# SCH_WINGLET_DISP.net
KiCad netlist of a schematic drawn in Altium Designer
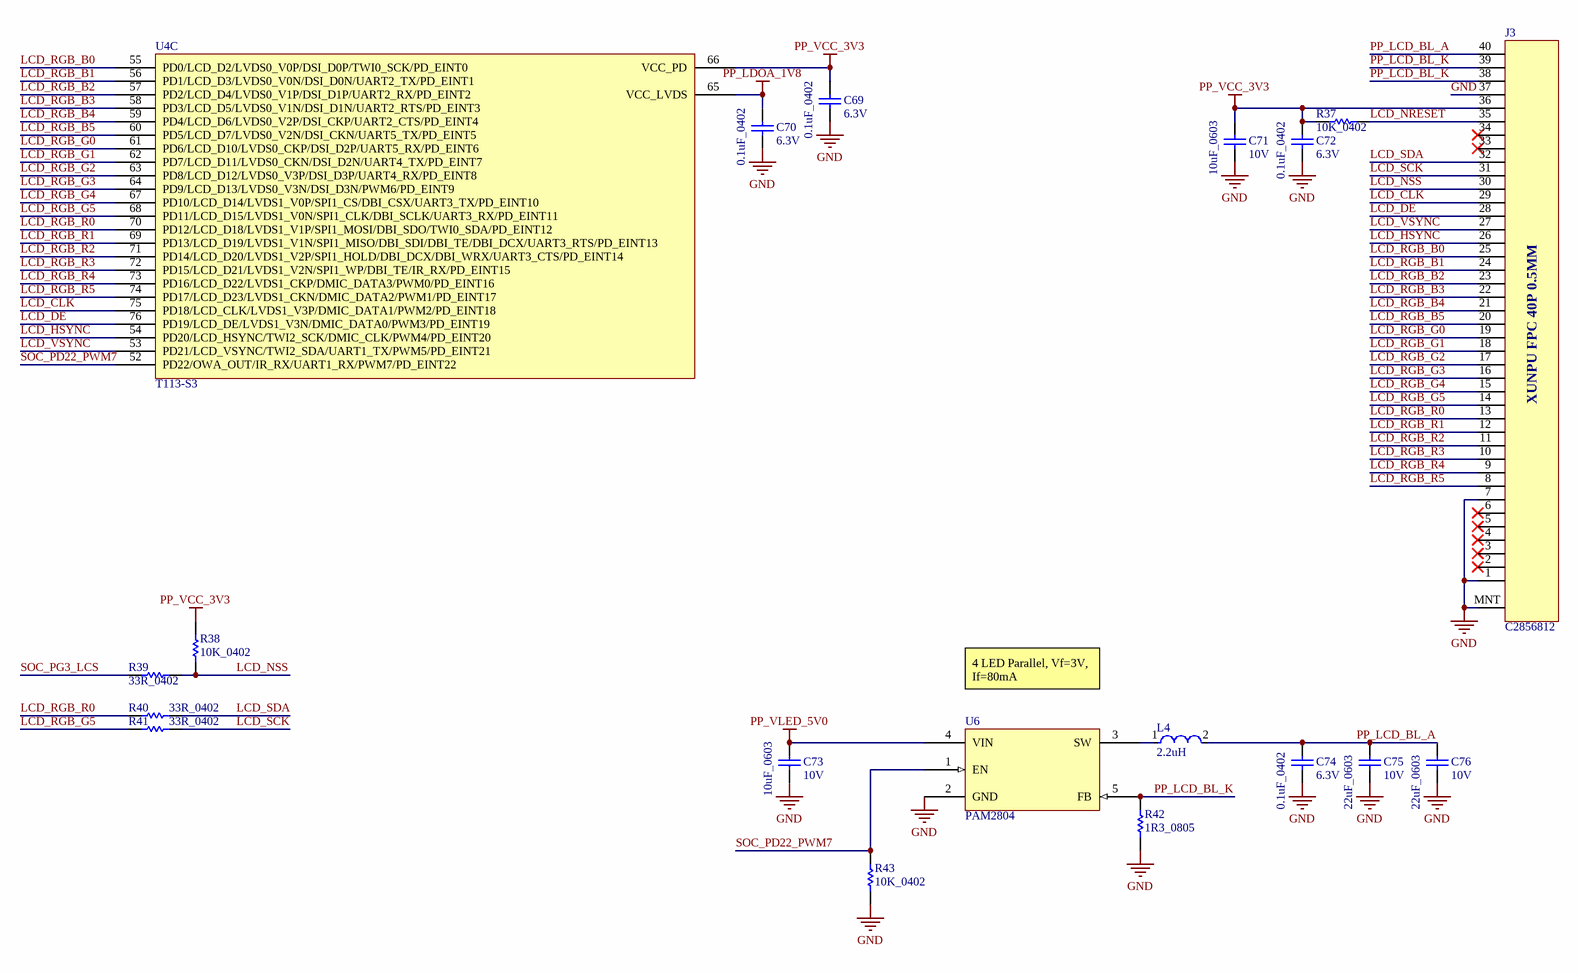
[diagram p0: SCH_WINGLET_DISP.SchDoc]

(export (version "E")
  (design (tool "Eeschema 10.0.6"))
  (components
    (comp (ref "C69")
      (value "0.1uF_0402")
      (footprint "CAPC1005X56X25NL10T15")
      (description "04026D104KAT2A")
      (fields (field (name "MANUFACTURER") "AVX Interconnect / Elco") (field (name "VOLTAGE RATING") "6.3V"))
      (libsource (lib "Altium Content Vault") (part "CAP"))
    )
    (comp (ref "C70")
      (value "0.1uF_0402")
      (footprint "CAPC1005X56X25NL10T15")
      (description "04026D104KAT2A")
      (fields (field (name "MANUFACTURER") "AVX Interconnect / Elco") (field (name "VOLTAGE RATING") "6.3V"))
      (libsource (lib "Altium Content Vault") (part "CAP"))
    )
    (comp (ref "C71")
      (value "10uF_0603")
      (footprint "CAPC1609X100X15NL20")
      (fields
        (field (name "PART NUMBER") "TACL106M006XTA")
        (field (name "MANUFACTURER") "AVX Interconnect / Elco")
        (field (name "VOLTAGE RATING") "10V")
      )
      (libsource (lib "Altium Content Vault") (part "CAP"))
    )
    (comp (ref "C72")
      (value "0.1uF_0402")
      (footprint "CAPC1005X56X25NL10T15")
      (description "04026D104KAT2A")
      (fields (field (name "MANUFACTURER") "AVX Interconnect / Elco") (field (name "VOLTAGE RATING") "6.3V"))
      (libsource (lib "Altium Content Vault") (part "CAP"))
    )
    (comp (ref "C73")
      (value "10uF_0603")
      (footprint "CAPC1609X100X15NL20")
      (fields
        (field (name "PART NUMBER") "TACL106M006XTA")
        (field (name "MANUFACTURER") "AVX Interconnect / Elco")
        (field (name "VOLTAGE RATING") "10V")
      )
      (libsource (lib "Altium Content Vault") (part "CAP"))
    )
    (comp (ref "C74")
      (value "0.1uF_0402")
      (footprint "CAPC1005X56X25NL10T15")
      (description "04026D104KAT2A")
      (fields (field (name "MANUFACTURER") "AVX Interconnect / Elco") (field (name "VOLTAGE RATING") "6.3V"))
      (libsource (lib "Altium Content Vault") (part "CAP"))
    )
    (comp (ref "C75")
      (value "22uF_0603")
      (footprint "CAPC1608X100X20NL10")
      (fields
        (field (name "MANUFACTURER") "TDK")
        (field (name "TOLERANCE") "±20%")
        (field (name "PCN PART NUMBER") "MLCCPartNumberChange30/Nov/2012")
        (field (name "VOLTAGE RATING") "10V")
      )
      (libsource (lib "Altium Content Vault") (part "CAP-NP-2"))
    )
    (comp (ref "C76")
      (value "22uF_0603")
      (footprint "CAPC1608X100X20NL10")
      (fields
        (field (name "MANUFACTURER") "TDK")
        (field (name "TOLERANCE") "±20%")
        (field (name "PCN PART NUMBER") "MLCCPartNumberChange30/Nov/2012")
        (field (name "VOLTAGE RATING") "10V")
      )
      (libsource (lib "Altium Content Vault") (part "CAP-NP-2"))
    )
    (comp (ref "J3")
      (value "C2856812")
      (footprint "LCSC_FPC_40P_0P5MM")
      (description "XUNPU FPC 40P 0.5MM\r\nC2856812")
      (libsource (lib "DCAV32_WINGLET_SCHLIB") (part "FPC-05F-40PH20"))
    )
    (comp (ref "L4")
      (value "2.2uH")
      (footprint "FP-NR3015-MFG")
      (description "SMD Power Inductors 2.2uH ±20% 1.48A 72mΩ\r\nNR3015T2R2M")
      (fields (field (name "TOLERANCE") "20%"))
      (libsource (lib "Altium Content Vault") (part "725321dda6339637d4d059423bc1c3c"))
    )
    (comp (ref "R37")
      (value "10K_0402")
      (footprint "RESC1005X40X25NL05T05")
      (fields (field (name "TOLERANCE") "1%") (field (name "MANUFACTURER") "Panasonic"))
      (libsource (lib "Altium Content Vault") (part "RES-2"))
    )
    (comp (ref "R38")
      (value "10K_0402")
      (footprint "RESC1005X40X25NL05T05")
      (fields (field (name "TOLERANCE") "1%") (field (name "MANUFACTURER") "Panasonic"))
      (libsource (lib "Altium Content Vault") (part "RES-2"))
    )
    (comp (ref "R39")
      (value "33R_0402")
      (footprint "RESC1005X40X25NL05T05")
      (description "ERJ2RKF33R0X")
      (fields (field (name "MANUFACTURER") "Panasonic"))
      (libsource (lib "Altium Content Vault") (part "RES"))
    )
    (comp (ref "R40")
      (value "33R_0402")
      (footprint "RESC1005X40X25NL05T05")
      (description "ERJ2RKF33R0X")
      (fields (field (name "MANUFACTURER") "Panasonic"))
      (libsource (lib "Altium Content Vault") (part "RES"))
    )
    (comp (ref "R41")
      (value "33R_0402")
      (footprint "RESC1005X40X25NL05T05")
      (description "ERJ2RKF33R0X")
      (fields (field (name "MANUFACTURER") "Panasonic"))
      (libsource (lib "Altium Content Vault") (part "RES"))
    )
    (comp (ref "R42")
      (value "1R3_0805")
      (footprint "RESC2013X50X30NL20T20")
      (description "CRCW08051R30JNEA")
      (fields (field (name "MANUFACTURER") "Vishay Dale"))
      (libsource (lib "Altium Content Vault") (part "RES"))
    )
    (comp (ref "R43")
      (value "10K_0402")
      (footprint "RESC1005X40X25NL05T05")
      (fields (field (name "TOLERANCE") "1%") (field (name "MANUFACTURER") "Panasonic"))
      (libsource (lib "Altium Content Vault") (part "RES-2"))
    )
    (comp (ref "U4")
      (value "T113-S3")
      (footprint "TSQFP40P1600X1600X160_HS-129N")
      (description "Allwinner Dual-core ARM Cortex-A7 Smart Control and Display SoC")
      (libsource (lib "DCAV32_WINGLET_SCHLIB") (part "T113-S3"))
    )
    (comp (ref "U6")
      (value "PAM2804")
      (footprint "SOT95P292X115-5N")
      (description "1A 1.5MHz STEP-DOWN CONSTANT CURRENT, HIGH EFFICIENCY LED DRIVER")
      (libsource (lib "DCAV32_WINGLET_SCHLIB") (part "PAM2804"))
    )
  )
  (nets
    (net (code "1") (name "/LCD_CLK") (class "Default")
      (node (ref "J3") (pin "29") (pintype "passive"))
      (node (ref "U4") (pin "75") (pinfunction "PD18/LCD_CLK/LVDS1_V3P/DMIC_DATA1/PWM2/PD_EINT18_75") (pintype "passive"))
    )
    (net (code "2") (name "/LCD_DE") (class "Default")
      (node (ref "J3") (pin "28") (pintype "passive"))
      (node (ref "U4") (pin "76") (pinfunction "PD19/LCD_DE/LVDS1_V3N/DMIC_DATA0/PWM3/PD_EINT19_76") (pintype "passive"))
    )
    (net (code "3") (name "/LCD_HSYNC") (class "Default")
      (node (ref "J3") (pin "26") (pintype "passive"))
      (node (ref "U4") (pin "54") (pinfunction "PD20/LCD_HSYNC/TWI2_SCK/DMIC_CLK/PWM4/PD_EINT20_54") (pintype "passive"))
    )
    (net (code "4") (name "/LCD_NRESET") (class "Default")
      (node (ref "J3") (pin "35") (pintype "passive"))
      (node (ref "R37") (pin "2") (pinfunction "2_2") (pintype "passive"))
    )
    (net (code "5") (name "/LCD_NSS") (class "Default")
      (node (ref "J3") (pin "30") (pintype "passive"))
      (node (ref "R38") (pin "2") (pinfunction "2_2") (pintype "passive"))
      (node (ref "R39") (pin "2") (pinfunction "2_2") (pintype "passive"))
    )
    (net (code "6") (name "/LCD_RGB_B0") (class "Default")
      (node (ref "J3") (pin "25") (pintype "passive"))
      (node (ref "U4") (pin "55") (pinfunction "PD0/LCD_D2/LVDS0_V0P/DSI_D0P/TWI0_SCK/PD_EINT0_55") (pintype "passive"))
    )
    (net (code "7") (name "/LCD_RGB_B1") (class "Default")
      (node (ref "J3") (pin "24") (pintype "passive"))
      (node (ref "U4") (pin "56") (pinfunction "PD1/LCD_D3/LVDS0_V0N/DSI_D0N/UART2_TX/PD_EINT1_56") (pintype "passive"))
    )
    (net (code "8") (name "/LCD_RGB_B2") (class "Default")
      (node (ref "J3") (pin "23") (pintype "passive"))
      (node (ref "U4") (pin "57") (pinfunction "PD2/LCD_D4/LVDS0_V1P/DSI_D1P/UART2_RX/PD_EINT2_57") (pintype "passive"))
    )
    (net (code "9") (name "/LCD_RGB_B3") (class "Default")
      (node (ref "J3") (pin "22") (pintype "passive"))
      (node (ref "U4") (pin "58") (pinfunction "PD3/LCD_D5/LVDS0_V1N/DSI_D1N/UART2_RTS/PD_EINT3_58") (pintype "passive"))
    )
    (net (code "10") (name "/LCD_RGB_B4") (class "Default")
      (node (ref "J3") (pin "21") (pintype "passive"))
      (node (ref "U4") (pin "59") (pinfunction "PD4/LCD_D6/LVDS0_V2P/DSI_CKP/UART2_CTS/PD_EINT4_59") (pintype "passive"))
    )
    (net (code "11") (name "/LCD_RGB_B5") (class "Default")
      (node (ref "J3") (pin "20") (pintype "passive"))
      (node (ref "U4") (pin "60") (pinfunction "PD5/LCD_D7/LVDS0_V2N/DSI_CKN/UART5_TX/PD_EINT5_60") (pintype "passive"))
    )
    (net (code "12") (name "/LCD_RGB_G0") (class "Default")
      (node (ref "J3") (pin "19") (pintype "passive"))
      (node (ref "U4") (pin "61") (pinfunction "PD6/LCD_D10/LVDS0_CKP/DSI_D2P/UART5_RX/PD_EINT6_61") (pintype "passive"))
    )
    (net (code "13") (name "/LCD_RGB_G1") (class "Default")
      (node (ref "J3") (pin "18") (pintype "passive"))
      (node (ref "U4") (pin "62") (pinfunction "PD7/LCD_D11/LVDS0_CKN/DSI_D2N/UART4_TX/PD_EINT7_62") (pintype "passive"))
    )
    (net (code "14") (name "/LCD_RGB_G2") (class "Default")
      (node (ref "J3") (pin "17") (pintype "passive"))
      (node (ref "U4") (pin "63") (pinfunction "PD8/LCD_D12/LVDS0_V3P/DSI_D3P/UART4_RX/PD_EINT8_63") (pintype "passive"))
    )
    (net (code "15") (name "/LCD_RGB_G3") (class "Default")
      (node (ref "J3") (pin "16") (pintype "passive"))
      (node (ref "U4") (pin "64") (pinfunction "PD9/LCD_D13/LVDS0_V3N/DSI_D3N/PWM6/PD_EINT9_64") (pintype "passive"))
    )
    (net (code "16") (name "/LCD_RGB_G4") (class "Default")
      (node (ref "J3") (pin "15") (pintype "passive"))
      (node (ref "U4") (pin "67") (pinfunction "PD10/LCD_D14/LVDS1_V0P/SPI1_CS/DBI_CSX/UART3_TX/PD_EINT10_67") (pintype "passive"))
    )
    (net (code "17") (name "/LCD_RGB_G5") (class "Default")
      (node (ref "J3") (pin "14") (pintype "passive"))
      (node (ref "R41") (pin "1") (pinfunction "1_1") (pintype "passive"))
      (node (ref "U4") (pin "68") (pinfunction "PD11/LCD_D15/LVDS1_V0N/SPI1_CLK/DBI_SCLK/UART3_RX/PD_EINT11_68") (pintype "passive"))
    )
    (net (code "18") (name "/LCD_RGB_R0") (class "Default")
      (node (ref "J3") (pin "13") (pintype "passive"))
      (node (ref "R40") (pin "1") (pinfunction "1_1") (pintype "passive"))
      (node (ref "U4") (pin "70") (pinfunction "PD12/LCD_D18/LVDS1_V1P/SPI1_MOSI/DBI_SDO/TWI0_SDA/PD_EINT12_70") (pintype "passive"))
    )
    (net (code "19") (name "/LCD_RGB_R1") (class "Default")
      (node (ref "J3") (pin "12") (pintype "passive"))
      (node (ref "U4") (pin "69") (pinfunction "PD13/LCD_D19/LVDS1_V1N/SPI1_MISO/DBI_SDI/DBI_TE/DBI_DCX/UART3_RTS/PD_EINT13_69") (pintype "passive"))
    )
    (net (code "20") (name "/LCD_RGB_R2") (class "Default")
      (node (ref "J3") (pin "11") (pintype "passive"))
      (node (ref "U4") (pin "71") (pinfunction "PD14/LCD_D20/LVDS1_V2P/SPI1_HOLD/DBI_DCX/DBI_WRX/UART3_CTS/PD_EINT14_71") (pintype "passive"))
    )
    (net (code "21") (name "/LCD_RGB_R3") (class "Default")
      (node (ref "J3") (pin "10") (pintype "passive"))
      (node (ref "U4") (pin "72") (pinfunction "PD15/LCD_D21/LVDS1_V2N/SPI1_WP/DBI_TE/IR_RX/PD_EINT15_72") (pintype "passive"))
    )
    (net (code "22") (name "/LCD_RGB_R4") (class "Default")
      (node (ref "J3") (pin "9") (pintype "passive"))
      (node (ref "U4") (pin "73") (pinfunction "PD16/LCD_D22/LVDS1_CKP/DMIC_DATA3/PWM0/PD_EINT16_73") (pintype "passive"))
    )
    (net (code "23") (name "/LCD_RGB_R5") (class "Default")
      (node (ref "J3") (pin "8") (pintype "passive"))
      (node (ref "U4") (pin "74") (pinfunction "PD17/LCD_D23/LVDS1_CKN/DMIC_DATA2/PWM1/PD_EINT17_74") (pintype "passive"))
    )
    (net (code "24") (name "/LCD_SCK") (class "Default")
      (node (ref "J3") (pin "31") (pintype "passive"))
      (node (ref "R41") (pin "2") (pinfunction "2_2") (pintype "passive"))
    )
    (net (code "25") (name "/LCD_SDA") (class "Default")
      (node (ref "J3") (pin "32") (pintype "passive"))
      (node (ref "R40") (pin "2") (pinfunction "2_2") (pintype "passive"))
    )
    (net (code "26") (name "/LCD_VSYNC") (class "Default")
      (node (ref "J3") (pin "27") (pintype "passive"))
      (node (ref "U4") (pin "53") (pinfunction "PD21/LCD_VSYNC/TWI2_SDA/UART1_TX/PWM5/PD_EINT21_53") (pintype "passive"))
    )
    (net (code "27") (name "/PP_LCD_BL_A") (class "Default")
      (node (ref "C74") (pin "2") (pinfunction "2_2") (pintype "passive"))
      (node (ref "C75") (pin "2") (pinfunction "2_2") (pintype "passive"))
      (node (ref "C76") (pin "2") (pinfunction "2_2") (pintype "passive"))
      (node (ref "J3") (pin "40") (pintype "passive"))
      (node (ref "L4") (pin "2") (pinfunction "2_2") (pintype "passive"))
    )
    (net (code "28") (name "/PP_LCD_BL_K") (class "Default")
      (node (ref "J3") (pin "38") (pintype "passive"))
      (node (ref "J3") (pin "39") (pintype "passive"))
      (node (ref "R42") (pin "2") (pinfunction "2_2") (pintype "passive"))
      (node (ref "U6") (pin "5") (pinfunction "FB_5") (pintype "input"))
    )
    (net (code "29") (name "/SOC_PD22_PWM7") (class "Default")
      (node (ref "R43") (pin "1") (pinfunction "1_1") (pintype "passive"))
      (node (ref "U4") (pin "52") (pinfunction "PD22/OWA_OUT/IR_RX/UART1_RX/PWM7/PD_EINT22_52") (pintype "passive"))
      (node (ref "U6") (pin "1") (pinfunction "EN_1") (pintype "input"))
    )
    (net (code "30") (name "/SOC_PG3_LCS") (class "Default")
      (node (ref "R39") (pin "1") (pinfunction "1_1") (pintype "passive"))
    )
    (net (code "31") (name "GND") (class "Default")
      (node (ref "C69") (pin "1") (pinfunction "1_1") (pintype "passive"))
      (node (ref "C70") (pin "1") (pinfunction "1_1") (pintype "passive"))
      (node (ref "C71") (pin "1") (pinfunction "1_1") (pintype "passive"))
      (node (ref "C72") (pin "1") (pinfunction "1_1") (pintype "passive"))
      (node (ref "C73") (pin "1") (pinfunction "1_1") (pintype "passive"))
      (node (ref "C74") (pin "1") (pinfunction "1_1") (pintype "passive"))
      (node (ref "C75") (pin "1") (pinfunction "1_1") (pintype "passive"))
      (node (ref "C76") (pin "1") (pinfunction "1_1") (pintype "passive"))
      (node (ref "J3") (pin "1") (pintype "passive"))
      (node (ref "J3") (pin "37") (pintype "passive"))
      (node (ref "J3") (pin "7") (pintype "passive"))
      (node (ref "J3") (pin "MNT") (pintype "passive"))
      (node (ref "R42") (pin "1") (pinfunction "1_1") (pintype "passive"))
      (node (ref "R43") (pin "2") (pinfunction "2_2") (pintype "passive"))
      (node (ref "U6") (pin "2") (pinfunction "GND_2") (pintype "passive"))
    )
    (net (code "32") (name "Net-(U6-SW)") (class "Default")
      (node (ref "L4") (pin "1") (pinfunction "1_1") (pintype "passive"))
      (node (ref "U6") (pin "3") (pinfunction "SW_3") (pintype "passive"))
    )
    (net (code "33") (name "PP_LDOA_1V8") (class "Default")
      (node (ref "C70") (pin "2") (pinfunction "2_2") (pintype "passive"))
      (node (ref "U4") (pin "65") (pinfunction "VCC_LVDS_65") (pintype "passive"))
    )
    (net (code "34") (name "PP_VCC_3V3") (class "Default")
      (node (ref "C69") (pin "2") (pinfunction "2_2") (pintype "passive"))
      (node (ref "C71") (pin "2") (pinfunction "2_2") (pintype "passive"))
      (node (ref "C72") (pin "2") (pinfunction "2_2") (pintype "passive"))
      (node (ref "J3") (pin "36") (pintype "passive"))
      (node (ref "R37") (pin "1") (pinfunction "1_1") (pintype "passive"))
      (node (ref "R38") (pin "1") (pinfunction "1_1") (pintype "passive"))
      (node (ref "U4") (pin "66") (pinfunction "VCC_PD_66") (pintype "passive"))
    )
    (net (code "35") (name "PP_VLED_5V0") (class "Default")
      (node (ref "C73") (pin "2") (pinfunction "2_2") (pintype "passive"))
      (node (ref "U6") (pin "4") (pinfunction "VIN_4") (pintype "passive"))
    )
    (net (code "36") (name "unconnected-(J3-Pad2)") (class "Default")
      (node (ref "J3") (pin "2") (pintype "passive+no_connect"))
    )
    (net (code "37") (name "unconnected-(J3-Pad3)") (class "Default")
      (node (ref "J3") (pin "3") (pintype "passive+no_connect"))
    )
    (net (code "38") (name "unconnected-(J3-Pad4)") (class "Default")
      (node (ref "J3") (pin "4") (pintype "passive+no_connect"))
    )
    (net (code "39") (name "unconnected-(J3-Pad5)") (class "Default")
      (node (ref "J3") (pin "5") (pintype "passive+no_connect"))
    )
    (net (code "40") (name "unconnected-(J3-Pad6)") (class "Default")
      (node (ref "J3") (pin "6") (pintype "passive+no_connect"))
    )
    (net (code "41") (name "unconnected-(J3-Pad33)") (class "Default")
      (node (ref "J3") (pin "33") (pintype "passive+no_connect"))
    )
    (net (code "42") (name "unconnected-(J3-Pad34)") (class "Default")
      (node (ref "J3") (pin "34") (pintype "passive+no_connect"))
    )
  )
)
